# current_driver.net
KiCad netlist of a schematic drawn in EAGLE
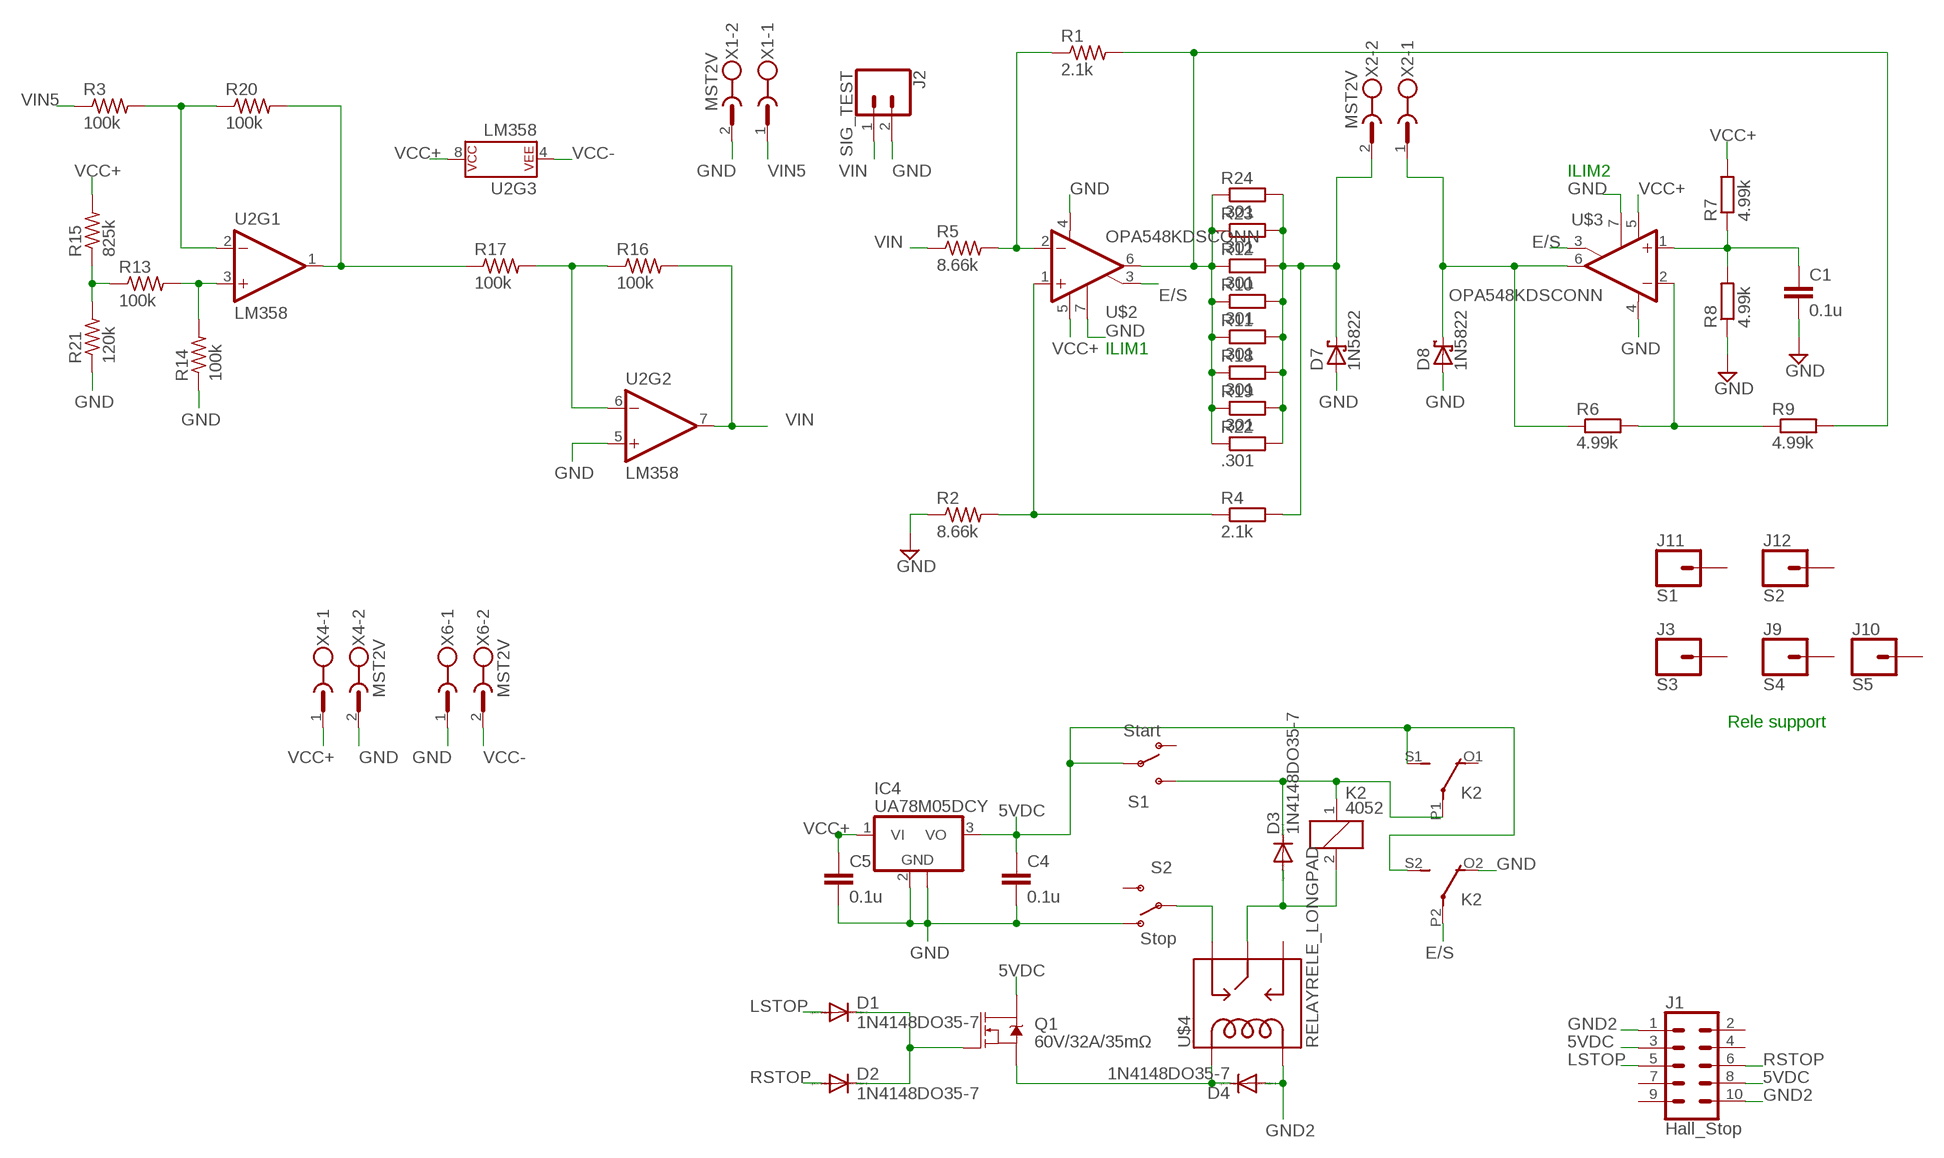
[diagram p0: schematic, sheet 1]

(export (version "E")
  (design (tool "Eeschema 10.0.6"))
  (components
    (comp (ref "C1")
      (value "0.1u")
      (footprint "eagle-import:C2012")
      (libsource (lib "eagle-import") (part "C-EUC2012"))
    )
    (comp (ref "C4")
      (value "0.1u")
      (footprint "eagle-import:C2012")
      (libsource (lib "eagle-import") (part "C-EUC2012"))
    )
    (comp (ref "C5")
      (value "0.1u")
      (footprint "eagle-import:C2012")
      (libsource (lib "eagle-import") (part "C-EUC2012"))
    )
    (comp (ref "D1")
      (value "1N4148DO35-7")
      (footprint "eagle-import:DO35-7")
      (libsource (lib "eagle-import") (part "1N4148DO35-7"))
    )
    (comp (ref "D2")
      (value "1N4148DO35-7")
      (footprint "eagle-import:DO35-7")
      (libsource (lib "eagle-import") (part "1N4148DO35-7"))
    )
    (comp (ref "D3")
      (value "1N4148DO35-7")
      (footprint "eagle-import:DO35-7")
      (libsource (lib "eagle-import") (part "1N4148DO35-7"))
    )
    (comp (ref "D4")
      (value "1N4148DO35-7")
      (footprint "eagle-import:DO35-7")
      (libsource (lib "eagle-import") (part "1N4148DO35-7"))
    )
    (comp (ref "D7")
      (value "1N5822")
      (footprint "eagle-import:F126Z12")
      (libsource (lib "eagle-import") (part "SCHOTTKY-DIODEF126Z12"))
    )
    (comp (ref "D8")
      (value "1N5822")
      (footprint "eagle-import:F126Z12")
      (libsource (lib "eagle-import") (part "SCHOTTKY-DIODEF126Z12"))
    )
    (comp (ref "IC4")
      (value "UA78M05DCY")
      (footprint "eagle-import:SOT223")
      (libsource (lib "eagle-import") (part "UA78MDCY05"))
    )
    (comp (ref "J1")
      (value "Hall_Stop")
      (footprint "eagle-import:2X5-SHROUDED_LOCK")
      (libsource (lib "eagle-import") (part "CONN_05X2SHD_LOCK"))
    )
    (comp (ref "J2")
      (value "SIG_TEST")
      (footprint "eagle-import:1X02_LOCK_LONGPADS")
      (libsource (lib "eagle-import") (part "CONN_02LOCK_LONGPADS"))
    )
    (comp (ref "J3")
      (value "S3")
      (footprint "eagle-import:1X01_LONGPAD")
      (libsource (lib "eagle-import") (part "CONN_01PTH_LONGPAD"))
    )
    (comp (ref "J9")
      (value "S4")
      (footprint "eagle-import:1X01_LONGPAD")
      (libsource (lib "eagle-import") (part "CONN_01PTH_LONGPAD"))
    )
    (comp (ref "J10")
      (value "S5")
      (footprint "eagle-import:1X01_LONGPAD")
      (libsource (lib "eagle-import") (part "CONN_01PTH_LONGPAD"))
    )
    (comp (ref "J11")
      (value "S1")
      (footprint "eagle-import:1X01_LONGPAD")
      (libsource (lib "eagle-import") (part "CONN_01PTH_LONGPAD"))
    )
    (comp (ref "J12")
      (value "S2")
      (footprint "eagle-import:1X01_LONGPAD")
      (libsource (lib "eagle-import") (part "CONN_01PTH_LONGPAD"))
    )
    (comp (ref "K2")
      (value "4052")
      (footprint "eagle-import:F4052")
      (libsource (lib "eagle-import") (part "4052"))
    )
    (comp (ref "Q1")
      (value "60V/32A/35mΩ")
      (footprint "eagle-import:TO220V")
      (libsource (lib "eagle-import") (part "MOSFET-NCH-FQP30N06L"))
    )
    (comp (ref "R1")
      (value "2.1k")
      (footprint "eagle-import:R0805")
      (libsource (lib "eagle-import") (part "R-US_R0805"))
    )
    (comp (ref "R2")
      (value "8.66k")
      (footprint "eagle-import:R0805")
      (libsource (lib "eagle-import") (part "R-US_R0805"))
    )
    (comp (ref "R3")
      (value "100k")
      (footprint "eagle-import:R0805")
      (libsource (lib "eagle-import") (part "R-US_R0805"))
    )
    (comp (ref "R4")
      (value "2.1k")
      (footprint "eagle-import:R0805")
      (libsource (lib "eagle-import") (part "resistor_R-EU_R0805"))
    )
    (comp (ref "R5")
      (value "8.66k")
      (footprint "eagle-import:R0805")
      (libsource (lib "eagle-import") (part "R-US_R0805"))
    )
    (comp (ref "R6")
      (value "4.99k")
      (footprint "eagle-import:R0805")
      (libsource (lib "eagle-import") (part "resistor_R-EU_R0805"))
    )
    (comp (ref "R7")
      (value "4.99k")
      (footprint "eagle-import:R0805")
      (libsource (lib "eagle-import") (part "resistor_R-EU_R0805"))
    )
    (comp (ref "R8")
      (value "4.99k")
      (footprint "eagle-import:R0805")
      (libsource (lib "eagle-import") (part "resistor_R-EU_R0805"))
    )
    (comp (ref "R9")
      (value "4.99k")
      (footprint "eagle-import:R0805")
      (libsource (lib "eagle-import") (part "resistor_R-EU_R0805"))
    )
    (comp (ref "R10")
      (value ".301")
      (footprint "eagle-import:M1206")
      (libsource (lib "eagle-import") (part "R-EU_M1206"))
    )
    (comp (ref "R11")
      (value ".301")
      (footprint "eagle-import:M1206")
      (libsource (lib "eagle-import") (part "R-EU_M1206"))
    )
    (comp (ref "R12")
      (value ".301")
      (footprint "eagle-import:M1206")
      (libsource (lib "eagle-import") (part "R-EU_M1206"))
    )
    (comp (ref "R13")
      (value "100k")
      (footprint "eagle-import:R0805")
      (libsource (lib "eagle-import") (part "R-US_R0805"))
    )
    (comp (ref "R14")
      (value "100k")
      (footprint "eagle-import:R0805")
      (libsource (lib "eagle-import") (part "R-US_R0805"))
    )
    (comp (ref "R15")
      (value "825k")
      (footprint "eagle-import:R0805")
      (libsource (lib "eagle-import") (part "R-US_R0805"))
    )
    (comp (ref "R16")
      (value "100k")
      (footprint "eagle-import:R0805")
      (libsource (lib "eagle-import") (part "R-US_R0805"))
    )
    (comp (ref "R17")
      (value "100k")
      (footprint "eagle-import:R0805")
      (libsource (lib "eagle-import") (part "R-US_R0805"))
    )
    (comp (ref "R18")
      (value ".301")
      (footprint "eagle-import:M1206")
      (libsource (lib "eagle-import") (part "R-EU_M1206"))
    )
    (comp (ref "R19")
      (value ".301")
      (footprint "eagle-import:M1206")
      (libsource (lib "eagle-import") (part "R-EU_M1206"))
    )
    (comp (ref "R20")
      (value "100k")
      (footprint "eagle-import:R0805")
      (libsource (lib "eagle-import") (part "R-US_R0805"))
    )
    (comp (ref "R21")
      (value "120k")
      (footprint "eagle-import:R0805")
      (libsource (lib "eagle-import") (part "R-US_R0805"))
    )
    (comp (ref "R22")
      (value ".301")
      (footprint "eagle-import:M1206")
      (libsource (lib "eagle-import") (part "R-EU_M1206"))
    )
    (comp (ref "R23")
      (value ".301")
      (footprint "eagle-import:M1206")
      (libsource (lib "eagle-import") (part "R-EU_M1206"))
    )
    (comp (ref "R24")
      (value ".301")
      (footprint "eagle-import:M1206")
      (libsource (lib "eagle-import") (part "R-EU_M1206"))
    )
    (comp (ref "S1")
      (value "Start")
      (footprint "eagle-import:SWITCH_SPDT_SMD")
      (libsource (lib "eagle-import") (part "SWITCH-SPDTSMD"))
    )
    (comp (ref "S2")
      (value "Stop")
      (footprint "eagle-import:SWITCH_SPDT_SMD")
      (libsource (lib "eagle-import") (part "SWITCH-SPDTSMD"))
    )
    (comp (ref "U$2")
      (value "OPA548KDSCONN")
      (footprint "eagle-import:OPA548KDSCONN")
      (libsource (lib "eagle-import") (part "OPA548KDSCONN"))
    )
    (comp (ref "U$3")
      (value "OPA548KDSCONN")
      (footprint "eagle-import:OPA548KDSCONN")
      (libsource (lib "eagle-import") (part "OPA548KDSCONN"))
    )
    (comp (ref "U$4")
      (value "RELAYRELE_LONGPAD")
      (footprint "eagle-import:RELE_LONGPAD")
      (libsource (lib "eagle-import") (part "RELAYRELE_LONGPAD"))
    )
    (comp (ref "U2")
      (value "LM358")
      (footprint "eagle-import:DIP08_LONGPAD")
      (libsource (lib "eagle-import") (part "LM358DIP08_LONGPAD"))
    )
    (comp (ref "X1")
      (value "MST2V")
      (footprint "eagle-import:MSTBV2")
      (libsource (lib "eagle-import") (part "MST2V"))
    )
    (comp (ref "X2")
      (value "MST2V")
      (footprint "eagle-import:MSTBV2")
      (libsource (lib "eagle-import") (part "MST2V"))
    )
    (comp (ref "X4")
      (value "MST2V")
      (footprint "eagle-import:MSTBV2")
      (libsource (lib "eagle-import") (part "MST2V"))
    )
    (comp (ref "X6")
      (value "MST2V")
      (footprint "eagle-import:MSTBV2")
      (libsource (lib "eagle-import") (part "MST2V"))
    )
  )
  (nets
    (net (code "1") (name "/5VDC") (class "Default")
      (node (ref "C4") (pin "1") (pinfunction "1_1") (pintype "passive"))
      (node (ref "IC4") (pin "3") (pinfunction "VO_3") (pintype "passive"))
      (node (ref "J1") (pin "3") (pinfunction "3_3") (pintype "passive"))
      (node (ref "J1") (pin "8") (pinfunction "8_8") (pintype "passive"))
      (node (ref "K2") (pin "S1") (pinfunction "S_S1") (pintype "passive"))
      (node (ref "K2") (pin "S2") (pinfunction "S_S2") (pintype "passive"))
      (node (ref "Q1") (pin "2") (pinfunction "D_2") (pintype "bidirectional"))
      (node (ref "S1") (pin "2") (pinfunction "P_2") (pintype "passive"))
    )
    (net (code "2") (name "/E{slash}S") (class "Default")
      (node (ref "K2") (pin "P2") (pinfunction "P_P2") (pintype "passive"))
      (node (ref "U$2") (pin "3") (pinfunction "ILIM_3") (pintype "input"))
      (node (ref "U$3") (pin "3") (pinfunction "ILIM_3") (pintype "input"))
    )
    (net (code "3") (name "/GND2") (class "Default")
      (node (ref "D4") (pin "A") (pinfunction "A_A") (pintype "passive"))
      (node (ref "J1") (pin "1") (pinfunction "1_1") (pintype "passive"))
      (node (ref "J1") (pin "10") (pinfunction "10_10") (pintype "passive"))
      (node (ref "U$4") (pin "COIL0") (pinfunction "COIL0_COIL0") (pintype "bidirectional"))
    )
    (net (code "4") (name "/LSTOP") (class "Default")
      (node (ref "D1") (pin "A") (pinfunction "A_A") (pintype "passive"))
      (node (ref "J1") (pin "5") (pinfunction "5_5") (pintype "passive"))
    )
    (net (code "5") (name "/RSTOP") (class "Default")
      (node (ref "D2") (pin "A") (pinfunction "A_A") (pintype "passive"))
      (node (ref "J1") (pin "6") (pinfunction "6_6") (pintype "passive"))
    )
    (net (code "6") (name "/VCC+") (class "Default")
      (node (ref "C5") (pin "1") (pinfunction "1_1") (pintype "passive"))
      (node (ref "IC4") (pin "1") (pinfunction "VI_1") (pintype "input"))
      (node (ref "R15") (pin "2") (pinfunction "2_2") (pintype "passive"))
      (node (ref "R7") (pin "2") (pinfunction "2_2") (pintype "passive"))
      (node (ref "U$2") (pin "5") (pinfunction "V+_5") (pintype "power_in"))
      (node (ref "U$3") (pin "5") (pinfunction "V+_5") (pintype "power_in"))
      (node (ref "U2") (pin "8") (pinfunction "P$V+_8") (pintype "bidirectional"))
      (node (ref "X4") (pin "1") (pinfunction "1_1") (pintype "passive"))
    )
    (net (code "7") (name "/VCC-") (class "Default")
      (node (ref "U2") (pin "4") (pinfunction "P$V-_4") (pintype "bidirectional"))
      (node (ref "X6") (pin "2") (pinfunction "1_2") (pintype "passive"))
    )
    (net (code "8") (name "/VIN") (class "Default")
      (node (ref "J2") (pin "1") (pinfunction "1_1") (pintype "passive"))
      (node (ref "R16") (pin "2") (pinfunction "2_2") (pintype "passive"))
      (node (ref "R5") (pin "1") (pinfunction "1_1") (pintype "passive"))
      (node (ref "U2") (pin "7") (pinfunction "OUT_7") (pintype "output"))
    )
    (net (code "9") (name "/VIN5") (class "Default")
      (node (ref "R3") (pin "1") (pinfunction "1_1") (pintype "passive"))
      (node (ref "X1") (pin "1") (pinfunction "1_1") (pintype "passive"))
    )
    (net (code "10") (name "GND") (class "Default")
      (node (ref "C1") (pin "2") (pinfunction "2_2") (pintype "passive"))
      (node (ref "C4") (pin "2") (pinfunction "2_2") (pintype "passive"))
      (node (ref "C5") (pin "2") (pinfunction "2_2") (pintype "passive"))
      (node (ref "D7") (pin "A") (pinfunction "A_A") (pintype "passive"))
      (node (ref "D8") (pin "A") (pinfunction "A_A") (pintype "passive"))
      (node (ref "IC4") (pin "2") (pinfunction "GND_2") (pintype "passive"))
      (node (ref "IC4") (pin "4") (pinfunction "GND_4") (pintype "passive"))
      (node (ref "J2") (pin "2") (pinfunction "2_2") (pintype "passive"))
      (node (ref "K2") (pin "O2") (pinfunction "O_O2") (pintype "passive"))
      (node (ref "R14") (pin "1") (pinfunction "1_1") (pintype "passive"))
      (node (ref "R2") (pin "1") (pinfunction "1_1") (pintype "passive"))
      (node (ref "R21") (pin "1") (pinfunction "1_1") (pintype "passive"))
      (node (ref "R8") (pin "1") (pinfunction "1_1") (pintype "passive"))
      (node (ref "S2") (pin "1") (pinfunction "O_1") (pintype "passive"))
      (node (ref "U$2") (pin "4") (pinfunction "V-_4") (pintype "power_in"))
      (node (ref "U$2") (pin "7") (pinfunction "E/S_7") (pintype "bidirectional"))
      (node (ref "U$3") (pin "4") (pinfunction "V-_4") (pintype "power_in"))
      (node (ref "U$3") (pin "7") (pinfunction "E/S_7") (pintype "bidirectional"))
      (node (ref "U2") (pin "5") (pinfunction "+IN_5") (pintype "input"))
      (node (ref "X1") (pin "2") (pinfunction "1_2") (pintype "passive"))
      (node (ref "X4") (pin "2") (pinfunction "1_2") (pintype "passive"))
      (node (ref "X6") (pin "1") (pinfunction "1_1") (pintype "passive"))
    )
    (net (code "11") (name "Net-(D3-PadA)") (class "Default")
      (node (ref "D3") (pin "A") (pinfunction "A_A") (pintype "passive"))
      (node (ref "K2") (pin "2") (pinfunction "2_2") (pintype "passive"))
      (node (ref "U$4") (pin "SWCOMMON") (pinfunction "SWCOMMON_SWCOMMON") (pintype "bidirectional"))
    )
    (net (code "12") (name "Net-(K2B-P)") (class "Default")
      (node (ref "D3") (pin "C") (pinfunction "C_C") (pintype "passive"))
      (node (ref "K2") (pin "1") (pinfunction "1_1") (pintype "passive"))
      (node (ref "K2") (pin "P1") (pinfunction "P_P1") (pintype "passive"))
      (node (ref "S1") (pin "3") (pinfunction "S_3") (pintype "passive"))
    )
    (net (code "13") (name "Net-(Q1-G)") (class "Default")
      (node (ref "D1") (pin "C") (pinfunction "C_C") (pintype "passive"))
      (node (ref "D2") (pin "C") (pinfunction "C_C") (pintype "passive"))
      (node (ref "Q1") (pin "1") (pinfunction "G_1") (pintype "bidirectional"))
    )
    (net (code "14") (name "Net-(Q1-S)") (class "Default")
      (node (ref "D4") (pin "C") (pinfunction "C_C") (pintype "passive"))
      (node (ref "Q1") (pin "3") (pinfunction "S_3") (pintype "bidirectional"))
      (node (ref "U$4") (pin "COIL1") (pinfunction "COIL1_COIL1") (pintype "bidirectional"))
    )
    (net (code "15") (name "Net-(R13-Pad1)") (class "Default")
      (node (ref "R13") (pin "1") (pinfunction "1_1") (pintype "passive"))
      (node (ref "R15") (pin "1") (pinfunction "1_1") (pintype "passive"))
      (node (ref "R21") (pin "2") (pinfunction "2_2") (pintype "passive"))
    )
    (net (code "16") (name "Net-(S2-P)") (class "Default")
      (node (ref "S2") (pin "2") (pinfunction "P_2") (pintype "passive"))
      (node (ref "U$4") (pin "SWCLOSED") (pinfunction "SWCLOSE_SWCLOSED") (pintype "bidirectional"))
    )
    (net (code "17") (name "Net-(U$2-+IN)") (class "Default")
      (node (ref "R2") (pin "2") (pinfunction "2_2") (pintype "passive"))
      (node (ref "R4") (pin "1") (pinfunction "1_1") (pintype "passive"))
      (node (ref "U$2") (pin "1") (pinfunction "+IN_1") (pintype "input"))
    )
    (net (code "18") (name "Net-(U$2--IN)") (class "Default")
      (node (ref "R1") (pin "1") (pinfunction "1_1") (pintype "passive"))
      (node (ref "R5") (pin "2") (pinfunction "2_2") (pintype "passive"))
      (node (ref "U$2") (pin "2") (pinfunction "-IN_2") (pintype "input"))
    )
    (net (code "19") (name "Net-(U$2-OUT)") (class "Default")
      (node (ref "R1") (pin "2") (pinfunction "2_2") (pintype "passive"))
      (node (ref "R10") (pin "1") (pinfunction "1_1") (pintype "passive"))
      (node (ref "R11") (pin "1") (pinfunction "1_1") (pintype "passive"))
      (node (ref "R12") (pin "1") (pinfunction "1_1") (pintype "passive"))
      (node (ref "R18") (pin "1") (pinfunction "1_1") (pintype "passive"))
      (node (ref "R19") (pin "1") (pinfunction "1_1") (pintype "passive"))
      (node (ref "R22") (pin "1") (pinfunction "1_1") (pintype "passive"))
      (node (ref "R23") (pin "1") (pinfunction "1_1") (pintype "passive"))
      (node (ref "R24") (pin "1") (pinfunction "1_1") (pintype "passive"))
      (node (ref "R9") (pin "2") (pinfunction "2_2") (pintype "passive"))
      (node (ref "U$2") (pin "6") (pinfunction "OUT_6") (pintype "output"))
    )
    (net (code "20") (name "Net-(U$3-+IN)") (class "Default")
      (node (ref "C1") (pin "1") (pinfunction "1_1") (pintype "passive"))
      (node (ref "R7") (pin "1") (pinfunction "1_1") (pintype "passive"))
      (node (ref "R8") (pin "2") (pinfunction "2_2") (pintype "passive"))
      (node (ref "U$3") (pin "1") (pinfunction "+IN_1") (pintype "input"))
    )
    (net (code "21") (name "Net-(U$3--IN)") (class "Default")
      (node (ref "R6") (pin "2") (pinfunction "2_2") (pintype "passive"))
      (node (ref "R9") (pin "1") (pinfunction "1_1") (pintype "passive"))
      (node (ref "U$3") (pin "2") (pinfunction "-IN_2") (pintype "input"))
    )
    (net (code "22") (name "Net-(U$3-OUT)") (class "Default")
      (node (ref "D8") (pin "C") (pinfunction "C_C") (pintype "passive"))
      (node (ref "R6") (pin "1") (pinfunction "1_1") (pintype "passive"))
      (node (ref "U$3") (pin "6") (pinfunction "OUT_6") (pintype "output"))
      (node (ref "X2") (pin "1") (pinfunction "1_1") (pintype "passive"))
    )
    (net (code "23") (name "Net-(U2A-+IN)") (class "Default")
      (node (ref "R13") (pin "2") (pinfunction "2_2") (pintype "passive"))
      (node (ref "R14") (pin "2") (pinfunction "2_2") (pintype "passive"))
      (node (ref "U2") (pin "3") (pinfunction "+IN_3") (pintype "input"))
    )
    (net (code "24") (name "Net-(U2A--IN)") (class "Default")
      (node (ref "R20") (pin "1") (pinfunction "1_1") (pintype "passive"))
      (node (ref "R3") (pin "2") (pinfunction "2_2") (pintype "passive"))
      (node (ref "U2") (pin "2") (pinfunction "-IN_2") (pintype "input"))
    )
    (net (code "25") (name "Net-(U2A-OUT)") (class "Default")
      (node (ref "R17") (pin "1") (pinfunction "1_1") (pintype "passive"))
      (node (ref "R20") (pin "2") (pinfunction "2_2") (pintype "passive"))
      (node (ref "U2") (pin "1") (pinfunction "OUT_1") (pintype "output"))
    )
    (net (code "26") (name "Net-(U2B--IN)") (class "Default")
      (node (ref "R16") (pin "1") (pinfunction "1_1") (pintype "passive"))
      (node (ref "R17") (pin "2") (pinfunction "2_2") (pintype "passive"))
      (node (ref "U2") (pin "6") (pinfunction "-IN_6") (pintype "input"))
    )
    (net (code "27") (name "Net-(X2B-1)") (class "Default")
      (node (ref "D7") (pin "C") (pinfunction "C_C") (pintype "passive"))
      (node (ref "R10") (pin "2") (pinfunction "2_2") (pintype "passive"))
      (node (ref "R11") (pin "2") (pinfunction "2_2") (pintype "passive"))
      (node (ref "R12") (pin "2") (pinfunction "2_2") (pintype "passive"))
      (node (ref "R18") (pin "2") (pinfunction "2_2") (pintype "passive"))
      (node (ref "R19") (pin "2") (pinfunction "2_2") (pintype "passive"))
      (node (ref "R22") (pin "2") (pinfunction "2_2") (pintype "passive"))
      (node (ref "R23") (pin "2") (pinfunction "2_2") (pintype "passive"))
      (node (ref "R24") (pin "2") (pinfunction "2_2") (pintype "passive"))
      (node (ref "R4") (pin "2") (pinfunction "2_2") (pintype "passive"))
      (node (ref "X2") (pin "2") (pinfunction "1_2") (pintype "passive"))
    )
    (net (code "28") (name "unconnected-(J1-Pad2)") (class "Default")
      (node (ref "J1") (pin "2") (pinfunction "2_2") (pintype "passive"))
    )
    (net (code "29") (name "unconnected-(J1-Pad4)") (class "Default")
      (node (ref "J1") (pin "4") (pinfunction "4_4") (pintype "passive"))
    )
    (net (code "30") (name "unconnected-(J1-Pad7)") (class "Default")
      (node (ref "J1") (pin "7") (pinfunction "7_7") (pintype "passive"))
    )
    (net (code "31") (name "unconnected-(J1-Pad9)") (class "Default")
      (node (ref "J1") (pin "9") (pinfunction "9_9") (pintype "passive"))
    )
    (net (code "32") (name "unconnected-(J3-Pad1)") (class "Default")
      (node (ref "J3") (pin "1") (pinfunction "1_1") (pintype "passive"))
    )
    (net (code "33") (name "unconnected-(J9-Pad1)") (class "Default")
      (node (ref "J9") (pin "1") (pinfunction "1_1") (pintype "passive"))
    )
    (net (code "34") (name "unconnected-(J10-Pad1)") (class "Default")
      (node (ref "J10") (pin "1") (pinfunction "1_1") (pintype "passive"))
    )
    (net (code "35") (name "unconnected-(J11-Pad1)") (class "Default")
      (node (ref "J11") (pin "1") (pinfunction "1_1") (pintype "passive"))
    )
    (net (code "36") (name "unconnected-(J12-Pad1)") (class "Default")
      (node (ref "J12") (pin "1") (pinfunction "1_1") (pintype "passive"))
    )
    (net (code "37") (name "unconnected-(K2B-O-PadO1)") (class "Default")
      (node (ref "K2") (pin "O1") (pinfunction "O_O1") (pintype "passive"))
    )
    (net (code "38") (name "unconnected-(S1-O-Pad1)") (class "Default")
      (node (ref "S1") (pin "1") (pinfunction "O_1") (pintype "passive"))
    )
    (net (code "39") (name "unconnected-(S2-S-Pad3)") (class "Default")
      (node (ref "S2") (pin "3") (pinfunction "S_3") (pintype "passive"))
    )
    (net (code "40") (name "unconnected-(U$4-PadSWOPEN)") (class "Default")
      (node (ref "U$4") (pin "SWOPEN") (pinfunction "SWOPEN_SWOPEN") (pintype "bidirectional"))
    )
  )
)
